# Unit-114.net
KiCad netlist of a schematic drawn in Altium Designer
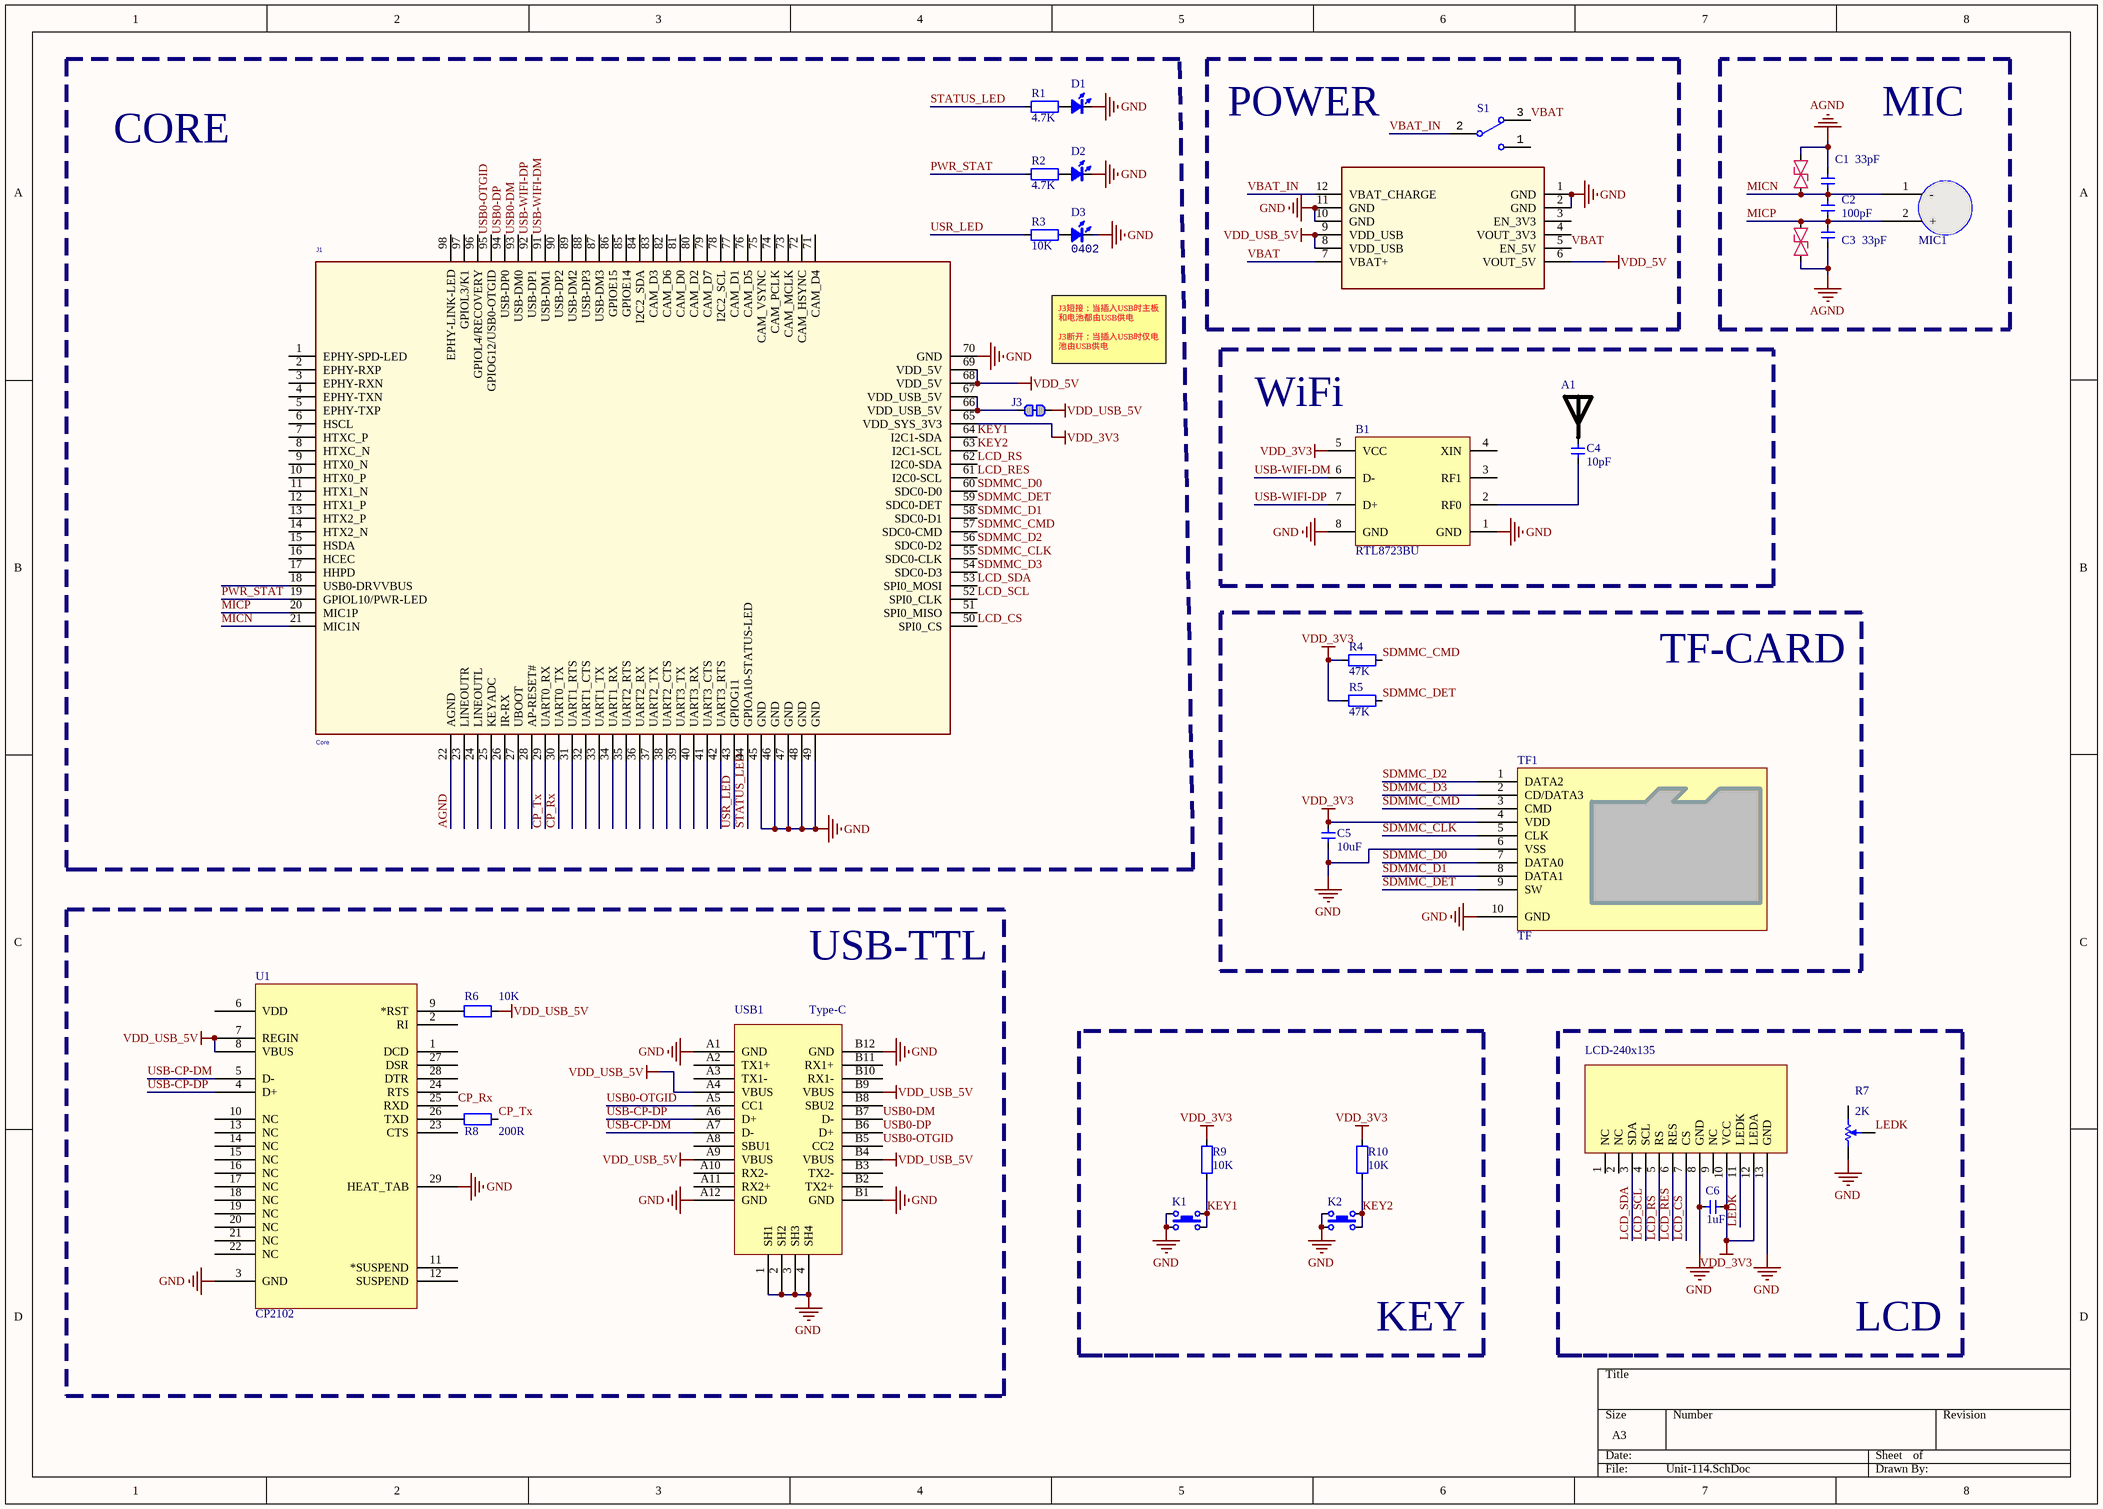
[diagram p0: Unit-114.SchDoc]

(export (version "E")
  (design (tool "Eeschema 10.0.6"))
  (components
    (comp (ref "1")
      (value "LCD-240x135")
      (footprint "LCD-240x135")
      (description "显示屏")
      (libsource (lib "MyPcbLib") (part "LCD-240x135"))
    )
    (comp (ref "A1")
      (value "RAINSUN")
      (footprint "ANT-Rainsun-AN5120")
      (libsource (lib "MyPcbLib") (part "ANT-Rainsun-AP5120"))
    )
    (comp (ref "B1")
      (value "RTL8723BU")
      (footprint "USB-WiFI-BT-RTL8723BU")
      (libsource (lib "MyPcbLib") (part "USB-WiFi-BT-RTL8723BU"))
    )
    (comp (ref "C1")
      (value "33pF")
      (footprint "CAP_0402")
      (description "Capacitor")
      (libsource (lib "MyPcbLib") (part "电容-0402"))
    )
    (comp (ref "C2")
      (value "100pF")
      (footprint "CAP_0402")
      (description "Capacitor")
      (libsource (lib "MyPcbLib") (part "电容-0402"))
    )
    (comp (ref "C3")
      (value "33pF")
      (footprint "CAP_0402")
      (description "Capacitor")
      (libsource (lib "MyPcbLib") (part "电容-0402"))
    )
    (comp (ref "C4")
      (value "10pF")
      (footprint "CAP_0402")
      (description "Capacitor")
      (libsource (lib "MyPcbLib") (part "电容-0402"))
    )
    (comp (ref "C5")
      (value "10uF")
      (footprint "CAP_0402")
      (description "Capacitor")
      (libsource (lib "MyPcbLib") (part "电容-0402"))
    )
    (comp (ref "C6")
      (value "1uF")
      (footprint "CAP_0402")
      (description "Capacitor")
      (libsource (lib "MyPcbLib") (part "电容-0402"))
    )
    (comp (ref "D1")
      (value "color?")
      (footprint "LED_0402_RED")
      (description "LED")
      (libsource (lib "KitSprout") (part "LED_0402"))
    )
    (comp (ref "D2")
      (value "color?")
      (footprint "LED_0402_YELLOW")
      (description "LED")
      (libsource (lib "KitSprout") (part "LED_0402"))
    )
    (comp (ref "D3")
      (value "color?")
      (footprint "LED_0402_BLUE")
      (description "LED")
      (fields (field (name "TYPE") "0402"))
      (libsource (lib "KitSprout") (part "LED_0402"))
    )
    (comp (ref "ESD-1")
      (value "ESD-0402")
      (footprint "ESD-0402")
      (description "ESD")
      (libsource (lib "MyPcbLib") (part "ESD-0402"))
    )
    (comp (ref "ESD-2")
      (value "ESD-0402")
      (footprint "ESD-0402")
      (description "ESD")
      (libsource (lib "MyPcbLib") (part "ESD-0402"))
    )
    (comp (ref "J1")
      (value "Core")
      (footprint "Quantum-Quark")
      (libsource (lib "mLib") (part "Quantum-Quark-Core"))
    )
    (comp (ref "J2")
      (value "Power")
      (footprint "Quantum-GLUON")
      (libsource (lib "MyPcbLib") (part "Quantum-Gluon-Power"))
    )
    (comp (ref "J3")
      (value "跳线")
      (footprint "0402-0R")
      (description "Resistor")
      (fields (field (name "PUBLISHER") "Altium Limited"))
      (libsource (lib "MyPcbLib") (part "跳线"))
    )
    (comp (ref "K1")
      (value "TACT 4P")
      (footprint "ButtonTACT_3.5*3.55_90")
      (description "Button")
      (libsource (lib "KitSprout") (part "ButtonTACT"))
    )
    (comp (ref "K2")
      (value "TACT 4P")
      (footprint "ButtonTACT_3.5*3.55_90")
      (description "Button")
      (libsource (lib "KitSprout") (part "ButtonTACT"))
    )
    (comp (ref "MIC1") (value "MIC*") (footprint "MIC-SMT") (libsource (lib "MyPcbLib") (part "MIC")))
    (comp (ref "R1")
      (value "4.7K")
      (footprint "RES_0402")
      (description "Resistor")
      (libsource (lib "MyPcbLib") (part "电阻-0402"))
    )
    (comp (ref "R2")
      (value "4.7K")
      (footprint "RES_0402")
      (description "Resistor")
      (libsource (lib "MyPcbLib") (part "电阻-0402"))
    )
    (comp (ref "R3")
      (value "10K")
      (footprint "RES_0402")
      (description "Resistor")
      (libsource (lib "MyPcbLib") (part "电阻-0402"))
    )
    (comp (ref "R4")
      (value "47K")
      (footprint "RES_0402")
      (description "Resistor")
      (libsource (lib "MyPcbLib") (part "电阻-0402"))
    )
    (comp (ref "R5")
      (value "47K")
      (footprint "RES_0402")
      (description "Resistor")
      (libsource (lib "MyPcbLib") (part "电阻-0402"))
    )
    (comp (ref "R6")
      (value "10K")
      (footprint "RES_0402")
      (description "Resistor")
      (libsource (lib "") (part "电阻-0402_2"))
    )
    (comp (ref "R7")
      (value "2K")
      (footprint "贴片电位器 3*3")
      (fields (field (name "PUBLISHER") "Altium Limited"))
      (libsource (lib "MyPcbLib") (part "电位器-贴片"))
    )
    (comp (ref "R8")
      (value "200R")
      (footprint "RES_0402")
      (description "Resistor")
      (libsource (lib "") (part "电阻-0402_2"))
    )
    (comp (ref "R9")
      (value "10K")
      (footprint "RES_0402")
      (description "Resistor")
      (libsource (lib "") (part "电阻-0402_1"))
    )
    (comp (ref "R10")
      (value "10K")
      (footprint "RES_0402")
      (description "Resistor")
      (libsource (lib "") (part "电阻-0402_1"))
    )
    (comp (ref "S1")
      (value "SPDT 3P")
      (footprint "SwitchSPDT_2.8X6.6_90")
      (description "Switch")
      (libsource (lib "KitSprout") (part "SwitchSPDT_2.8x6.6_90"))
    )
    (comp (ref "TF1")
      (value "TF")
      (footprint "TF-SOCKET - short")
      (description "8脚自弹")
      (libsource (lib "MyPcbLib") (part "TF卡座"))
    )
    (comp (ref "U1")
      (value "CP2102")
      (footprint "QFN-28")
      (description "USB转TTL")
      (libsource (lib "mLib") (part "CP2102"))
    )
    (comp (ref "USB1")
      (value "Type-C")
      (footprint "Type-C-TOP")
      (libsource (lib "MyPcbLib") (part "USB-Type-C-TOP"))
    )
  )
  (nets
    (net (code "1") (name "/CP_Rx") (class "Default")
      (node (ref "J1") (pin "30") (pinfunction "UART0_TX_30") (pintype "passive"))
      (node (ref "U1") (pin "25") (pinfunction "RXD_25") (pintype "passive"))
    )
    (net (code "2") (name "/CP_Tx") (class "Default")
      (node (ref "J1") (pin "29") (pinfunction "UART0_RX_29") (pintype "passive"))
      (node (ref "R8") (pin "1") (pinfunction "1_1") (pintype "passive"))
    )
    (net (code "3") (name "/KEY1") (class "Default")
      (node (ref "J1") (pin "64") (pinfunction "I2C1-SDA_64") (pintype "passive"))
      (node (ref "K1") (pin "2") (pinfunction "2_2") (pintype "passive"))
      (node (ref "K1") (pin "4") (pinfunction "4_4") (pintype "passive"))
      (node (ref "R9") (pin "1") (pinfunction "1_1") (pintype "passive"))
    )
    (net (code "4") (name "/KEY2") (class "Default")
      (node (ref "J1") (pin "63") (pinfunction "I2C1-SCL_63") (pintype "passive"))
      (node (ref "K2") (pin "2") (pinfunction "2_2") (pintype "passive"))
      (node (ref "K2") (pin "4") (pinfunction "4_4") (pintype "passive"))
      (node (ref "R10") (pin "1") (pinfunction "1_1") (pintype "passive"))
    )
    (net (code "5") (name "/LCD_CS") (class "Default")
      (node (ref "1") (pin "7") (pinfunction "CS_7") (pintype "passive"))
      (node (ref "J1") (pin "50") (pinfunction "SPI0_CS_50") (pintype "passive"))
    )
    (net (code "6") (name "/LCD_RES") (class "Default")
      (node (ref "1") (pin "6") (pinfunction "RES_6") (pintype "passive"))
      (node (ref "J1") (pin "61") (pinfunction "I2C0-SCL_61") (pintype "passive"))
    )
    (net (code "7") (name "/LCD_RS") (class "Default")
      (node (ref "1") (pin "5") (pinfunction "RS_5") (pintype "passive"))
      (node (ref "J1") (pin "62") (pinfunction "I2C0-SDA_62") (pintype "passive"))
    )
    (net (code "8") (name "/LCD_SCL") (class "Default")
      (node (ref "1") (pin "4") (pinfunction "SCL_4") (pintype "passive"))
      (node (ref "J1") (pin "52") (pinfunction "SPI0_CLK_52") (pintype "passive"))
    )
    (net (code "9") (name "/LCD_SDA") (class "Default")
      (node (ref "1") (pin "3") (pinfunction "SDA_3") (pintype "passive"))
      (node (ref "J1") (pin "53") (pinfunction "SPI0_MOSI_53") (pintype "passive"))
    )
    (net (code "10") (name "/LEDK") (class "Default")
      (node (ref "1") (pin "11") (pinfunction "LEDK_11") (pintype "passive"))
      (node (ref "R7") (pin "3") (pinfunction "W_3") (pintype "passive"))
    )
    (net (code "11") (name "/MICN") (class "Default")
      (node (ref "C1") (pin "2") (pinfunction "2_2") (pintype "passive"))
      (node (ref "C2") (pin "2") (pinfunction "2_2") (pintype "passive"))
      (node (ref "ESD-1") (pin "1") (pinfunction "1_1") (pintype "passive"))
      (node (ref "J1") (pin "21") (pinfunction "MIC1N_21") (pintype "passive"))
      (node (ref "MIC1") (pin "1") (pinfunction "-_1") (pintype "passive"))
    )
    (net (code "12") (name "/MICP") (class "Default")
      (node (ref "C2") (pin "1") (pinfunction "1_1") (pintype "passive"))
      (node (ref "C3") (pin "2") (pinfunction "2_2") (pintype "passive"))
      (node (ref "ESD-2") (pin "2") (pinfunction "2_2") (pintype "passive"))
      (node (ref "J1") (pin "20") (pinfunction "MIC1P_20") (pintype "passive"))
      (node (ref "MIC1") (pin "2") (pinfunction "+_2") (pintype "passive"))
    )
    (net (code "13") (name "/PWR_STAT") (class "Default")
      (node (ref "J1") (pin "19") (pinfunction "GPIOL10/PWR-LED_19") (pintype "passive"))
      (node (ref "R2") (pin "1") (pinfunction "1_1") (pintype "passive"))
    )
    (net (code "14") (name "/SDMMC_CLK") (class "Default")
      (node (ref "J1") (pin "55") (pinfunction "SDC0-CLK_55") (pintype "passive"))
      (node (ref "TF1") (pin "5") (pinfunction "CLK_5") (pintype "passive"))
    )
    (net (code "15") (name "/SDMMC_CMD") (class "Default")
      (node (ref "J1") (pin "57") (pinfunction "SDC0-CMD_57") (pintype "passive"))
      (node (ref "R4") (pin "2") (pinfunction "2_2") (pintype "passive"))
      (node (ref "TF1") (pin "3") (pinfunction "CMD_3") (pintype "passive"))
    )
    (net (code "16") (name "/SDMMC_D0") (class "Default")
      (node (ref "J1") (pin "60") (pinfunction "SDC0-D0_60") (pintype "passive"))
      (node (ref "TF1") (pin "7") (pinfunction "DATA0_7") (pintype "passive"))
    )
    (net (code "17") (name "/SDMMC_D1") (class "Default")
      (node (ref "J1") (pin "58") (pinfunction "SDC0-D1_58") (pintype "passive"))
      (node (ref "TF1") (pin "8") (pinfunction "DATA1_8") (pintype "passive"))
    )
    (net (code "18") (name "/SDMMC_D2") (class "Default")
      (node (ref "J1") (pin "56") (pinfunction "SDC0-D2_56") (pintype "passive"))
      (node (ref "TF1") (pin "1") (pinfunction "DATA2_1") (pintype "passive"))
    )
    (net (code "19") (name "/SDMMC_D3") (class "Default")
      (node (ref "J1") (pin "54") (pinfunction "SDC0-D3_54") (pintype "passive"))
      (node (ref "TF1") (pin "2") (pinfunction "CD/DATA3_2") (pintype "passive"))
    )
    (net (code "20") (name "/SDMMC_DET") (class "Default")
      (node (ref "J1") (pin "59") (pinfunction "SDC0-DET_59") (pintype "passive"))
      (node (ref "R5") (pin "2") (pinfunction "2_2") (pintype "passive"))
      (node (ref "TF1") (pin "9") (pinfunction "SW_9") (pintype "passive"))
    )
    (net (code "21") (name "/STATUS_LED") (class "Default")
      (node (ref "J1") (pin "44") (pinfunction "GPIOA10-STATUS-LED_44") (pintype "passive"))
      (node (ref "R1") (pin "1") (pinfunction "1_1") (pintype "passive"))
    )
    (net (code "22") (name "/USB-CP-DM") (class "Default")
      (node (ref "U1") (pin "5") (pinfunction "D-_5") (pintype "passive"))
      (node (ref "USB1") (pin "A7") (pinfunction "D-_A7") (pintype "passive"))
    )
    (net (code "23") (name "/USB-CP-DP") (class "Default")
      (node (ref "U1") (pin "4") (pinfunction "D+_4") (pintype "passive"))
      (node (ref "USB1") (pin "A6") (pinfunction "D+_A6") (pintype "passive"))
    )
    (net (code "24") (name "/USB-WIFI-DM") (class "Default")
      (node (ref "B1") (pin "6") (pinfunction "D-_6") (pintype "passive"))
      (node (ref "J1") (pin "91") (pinfunction "USB-DM1_91") (pintype "passive"))
    )
    (net (code "25") (name "/USB-WIFI-DP") (class "Default")
      (node (ref "B1") (pin "7") (pinfunction "D+_7") (pintype "passive"))
      (node (ref "J1") (pin "92") (pinfunction "USB-DP1_92") (pintype "passive"))
    )
    (net (code "26") (name "/USB0-DM") (class "Default")
      (node (ref "J1") (pin "93") (pinfunction "USB-DM0_93") (pintype "passive"))
      (node (ref "USB1") (pin "B7") (pinfunction "D-_B7") (pintype "passive"))
    )
    (net (code "27") (name "/USB0-DP") (class "Default")
      (node (ref "J1") (pin "94") (pinfunction "USB-DP0_94") (pintype "passive"))
      (node (ref "USB1") (pin "B6") (pinfunction "D+_B6") (pintype "passive"))
    )
    (net (code "28") (name "/USB0-OTGID") (class "Default")
      (node (ref "J1") (pin "95") (pinfunction "GPIOG12/USB0-OTGID_95") (pintype "passive"))
      (node (ref "USB1") (pin "A5") (pinfunction "CC1_A5") (pintype "passive"))
      (node (ref "USB1") (pin "B5") (pinfunction "CC2_B5") (pintype "passive"))
    )
    (net (code "29") (name "/USR_LED") (class "Default")
      (node (ref "J1") (pin "43") (pinfunction "GPIOG11_43") (pintype "passive"))
      (node (ref "R3") (pin "1") (pinfunction "1_1") (pintype "passive"))
    )
    (net (code "30") (name "/VBAT") (class "Default")
      (node (ref "J2") (pin "5") (pinfunction "EN_5V_5") (pintype "passive"))
      (node (ref "J2") (pin "7") (pinfunction "VBAT+_7") (pintype "passive"))
      (node (ref "S1") (pin "3") (pinfunction "3_3") (pintype "passive"))
    )
    (net (code "31") (name "/VBAT_IN") (class "Default")
      (node (ref "J2") (pin "12") (pinfunction "VBAT_CHARGE_12") (pintype "passive"))
      (node (ref "S1") (pin "2") (pinfunction "2_2") (pintype "passive"))
    )
    (net (code "32") (name "AGND") (class "Default")
      (node (ref "C1") (pin "1") (pinfunction "1_1") (pintype "passive"))
      (node (ref "C3") (pin "1") (pinfunction "1_1") (pintype "passive"))
      (node (ref "ESD-1") (pin "2") (pinfunction "2_2") (pintype "passive"))
      (node (ref "ESD-2") (pin "1") (pinfunction "1_1") (pintype "passive"))
      (node (ref "J1") (pin "22") (pinfunction "AGND_22") (pintype "passive"))
    )
    (net (code "33") (name "GND") (class "Default")
      (node (ref "1") (pin "13") (pinfunction "GND_13") (pintype "passive"))
      (node (ref "1") (pin "8") (pinfunction "GND_8") (pintype "passive"))
      (node (ref "B1") (pin "1") (pinfunction "GND_1") (pintype "passive"))
      (node (ref "B1") (pin "8") (pinfunction "GND_8") (pintype "passive"))
      (node (ref "C5") (pin "1") (pinfunction "1_1") (pintype "passive"))
      (node (ref "C6") (pin "2") (pinfunction "2_2") (pintype "passive"))
      (node (ref "D1") (pin "2") (pinfunction "K_2") (pintype "passive"))
      (node (ref "D2") (pin "2") (pinfunction "K_2") (pintype "passive"))
      (node (ref "D3") (pin "2") (pinfunction "K_2") (pintype "passive"))
      (node (ref "J1") (pin "45") (pinfunction "GND_45") (pintype "passive"))
      (node (ref "J1") (pin "46") (pinfunction "GND_46") (pintype "passive"))
      (node (ref "J1") (pin "47") (pinfunction "GND_47") (pintype "passive"))
      (node (ref "J1") (pin "48") (pinfunction "GND_48") (pintype "passive"))
      (node (ref "J1") (pin "49") (pinfunction "GND_49") (pintype "passive"))
      (node (ref "J1") (pin "70") (pinfunction "GND_70") (pintype "passive"))
      (node (ref "J2") (pin "1") (pinfunction "GND_1") (pintype "passive"))
      (node (ref "J2") (pin "10") (pinfunction "GND_10") (pintype "passive"))
      (node (ref "J2") (pin "11") (pinfunction "GND_11") (pintype "passive"))
      (node (ref "J2") (pin "2") (pinfunction "GND_2") (pintype "passive"))
      (node (ref "K1") (pin "1") (pinfunction "1_1") (pintype "passive"))
      (node (ref "K1") (pin "3") (pinfunction "3_3") (pintype "passive"))
      (node (ref "K2") (pin "1") (pinfunction "1_1") (pintype "passive"))
      (node (ref "K2") (pin "3") (pinfunction "3_3") (pintype "passive"))
      (node (ref "R7") (pin "2") (pinfunction "-_2") (pintype "passive"))
      (node (ref "TF1") (pin "10") (pinfunction "GND_10") (pintype "passive"))
      (node (ref "TF1") (pin "6") (pinfunction "VSS_6") (pintype "passive"))
      (node (ref "U1") (pin "29") (pinfunction "HEAT_TAB_29") (pintype "passive"))
      (node (ref "U1") (pin "3") (pinfunction "GND_3") (pintype "passive"))
      (node (ref "USB1") (pin "1") (pinfunction "SH1_1") (pintype "passive"))
      (node (ref "USB1") (pin "2") (pinfunction "SH2_2") (pintype "passive"))
      (node (ref "USB1") (pin "3") (pinfunction "SH3_3") (pintype "passive"))
      (node (ref "USB1") (pin "4") (pinfunction "SH4_4") (pintype "passive"))
      (node (ref "USB1") (pin "A1") (pinfunction "GND_A1") (pintype "passive"))
      (node (ref "USB1") (pin "A12") (pinfunction "GND_A12") (pintype "passive"))
      (node (ref "USB1") (pin "B1") (pinfunction "GND_B1") (pintype "passive"))
      (node (ref "USB1") (pin "B12") (pinfunction "GND_B12") (pintype "passive"))
    )
    (net (code "34") (name "Net-(A1-Pad1)") (class "Default")
      (node (ref "A1") (pin "1") (pinfunction "1_1") (pintype "passive"))
      (node (ref "C4") (pin "1") (pinfunction "1_1") (pintype "passive"))
    )
    (net (code "35") (name "Net-(B1-RF0)") (class "Default")
      (node (ref "B1") (pin "2") (pinfunction "RF0_2") (pintype "passive"))
      (node (ref "C4") (pin "2") (pinfunction "2_2") (pintype "passive"))
    )
    (net (code "36") (name "Net-(D1-A)") (class "Default")
      (node (ref "D1") (pin "1") (pinfunction "A_1") (pintype "passive"))
      (node (ref "R1") (pin "2") (pinfunction "2_2") (pintype "passive"))
    )
    (net (code "37") (name "Net-(D2-A)") (class "Default")
      (node (ref "D2") (pin "1") (pinfunction "A_1") (pintype "passive"))
      (node (ref "R2") (pin "2") (pinfunction "2_2") (pintype "passive"))
    )
    (net (code "38") (name "Net-(D3-A)") (class "Default")
      (node (ref "D3") (pin "1") (pinfunction "A_1") (pintype "passive"))
      (node (ref "R3") (pin "2") (pinfunction "2_2") (pintype "passive"))
    )
    (net (code "39") (name "Net-(J1-VDD_USB_5V-Pad66)") (class "Default")
      (node (ref "J1") (pin "66") (pinfunction "VDD_USB_5V_66") (pintype "passive"))
      (node (ref "J1") (pin "67") (pinfunction "VDD_USB_5V_67") (pintype "passive"))
      (node (ref "J3") (pin "1") (pinfunction "1_1") (pintype "passive"))
    )
    (net (code "40") (name "Net-(U1-*RST)") (class "Default")
      (node (ref "R6") (pin "2") (pinfunction "2_2") (pintype "passive"))
      (node (ref "U1") (pin "9") (pinfunction "*RST_9") (pintype "passive"))
    )
    (net (code "41") (name "Net-(U1-TXD)") (class "Default")
      (node (ref "R8") (pin "2") (pinfunction "2_2") (pintype "passive"))
      (node (ref "U1") (pin "26") (pinfunction "TXD_26") (pintype "passive"))
    )
    (net (code "42") (name "VDD_3V3") (class "Default")
      (node (ref "1") (pin "10") (pinfunction "VCC_10") (pintype "passive"))
      (node (ref "1") (pin "12") (pinfunction "LEDA_12") (pintype "passive"))
      (node (ref "B1") (pin "5") (pinfunction "VCC_5") (pintype "passive"))
      (node (ref "C5") (pin "2") (pinfunction "2_2") (pintype "passive"))
      (node (ref "C6") (pin "1") (pinfunction "1_1") (pintype "passive"))
      (node (ref "J1") (pin "65") (pinfunction "VDD_SYS_3V3_65") (pintype "passive"))
      (node (ref "R10") (pin "2") (pinfunction "2_2") (pintype "passive"))
      (node (ref "R4") (pin "1") (pinfunction "1_1") (pintype "passive"))
      (node (ref "R5") (pin "1") (pinfunction "1_1") (pintype "passive"))
      (node (ref "R9") (pin "2") (pinfunction "2_2") (pintype "passive"))
      (node (ref "TF1") (pin "4") (pinfunction "VDD_4") (pintype "passive"))
    )
    (net (code "43") (name "VDD_5V") (class "Default")
      (node (ref "J1") (pin "68") (pinfunction "VDD_5V_68") (pintype "passive"))
      (node (ref "J1") (pin "69") (pinfunction "VDD_5V_69") (pintype "passive"))
      (node (ref "J2") (pin "6") (pinfunction "VOUT_5V_6") (pintype "passive"))
    )
    (net (code "44") (name "VDD_USB_5V") (class "Default")
      (node (ref "J2") (pin "8") (pinfunction "VDD_USB_8") (pintype "passive"))
      (node (ref "J2") (pin "9") (pinfunction "VDD_USB_9") (pintype "passive"))
      (node (ref "J3") (pin "2") (pinfunction "2_2") (pintype "passive"))
      (node (ref "R6") (pin "1") (pinfunction "1_1") (pintype "passive"))
      (node (ref "U1") (pin "7") (pinfunction "REGIN_7") (pintype "passive"))
      (node (ref "U1") (pin "8") (pinfunction "VBUS_8") (pintype "passive"))
      (node (ref "USB1") (pin "A4") (pinfunction "VBUS_A4") (pintype "passive"))
      (node (ref "USB1") (pin "A9") (pinfunction "VBUS_A9") (pintype "passive"))
      (node (ref "USB1") (pin "B4") (pinfunction "VBUS_B4") (pintype "passive"))
      (node (ref "USB1") (pin "B9") (pinfunction "VBUS_B9") (pintype "passive"))
    )
    (net (code "45") (name "unconnected-(1-NC-Pad1)") (class "Default")
      (node (ref "1") (pin "1") (pinfunction "NC_1") (pintype "passive"))
    )
    (net (code "46") (name "unconnected-(1-NC-Pad2)") (class "Default")
      (node (ref "1") (pin "2") (pinfunction "NC_2") (pintype "passive"))
    )
    (net (code "47") (name "unconnected-(1-NC-Pad9)") (class "Default")
      (node (ref "1") (pin "9") (pinfunction "NC_9") (pintype "passive"))
    )
    (net (code "48") (name "unconnected-(B1-RF1-Pad3)") (class "Default")
      (node (ref "B1") (pin "3") (pinfunction "RF1_3") (pintype "passive"))
    )
    (net (code "49") (name "unconnected-(B1-XIN-Pad4)") (class "Default")
      (node (ref "B1") (pin "4") (pinfunction "XIN_4") (pintype "passive"))
    )
    (net (code "50") (name "unconnected-(J1-AP-RESET#-Pad28)") (class "Default")
      (node (ref "J1") (pin "28") (pinfunction "AP-RESET#_28") (pintype "passive"))
    )
    (net (code "51") (name "unconnected-(J1-CAM_D0-Pad81)") (class "Default")
      (node (ref "J1") (pin "81") (pinfunction "CAM_D0_81") (pintype "passive"))
    )
    (net (code "52") (name "unconnected-(J1-CAM_D1-Pad77)") (class "Default")
      (node (ref "J1") (pin "77") (pinfunction "CAM_D1_77") (pintype "passive"))
    )
    (net (code "53") (name "unconnected-(J1-CAM_D2-Pad80)") (class "Default")
      (node (ref "J1") (pin "80") (pinfunction "CAM_D2_80") (pintype "passive"))
    )
    (net (code "54") (name "unconnected-(J1-CAM_D3-Pad83)") (class "Default")
      (node (ref "J1") (pin "83") (pinfunction "CAM_D3_83") (pintype "passive"))
    )
    (net (code "55") (name "unconnected-(J1-CAM_D4-Pad71)") (class "Default")
      (node (ref "J1") (pin "71") (pinfunction "CAM_D4_71") (pintype "passive"))
    )
    (net (code "56") (name "unconnected-(J1-CAM_D5-Pad76)") (class "Default")
      (node (ref "J1") (pin "76") (pinfunction "CAM_D5_76") (pintype "passive"))
    )
    (net (code "57") (name "unconnected-(J1-CAM_D6-Pad82)") (class "Default")
      (node (ref "J1") (pin "82") (pinfunction "CAM_D6_82") (pintype "passive"))
    )
    (net (code "58") (name "unconnected-(J1-CAM_D7-Pad79)") (class "Default")
      (node (ref "J1") (pin "79") (pinfunction "CAM_D7_79") (pintype "passive"))
    )
    (net (code "59") (name "unconnected-(J1-CAM_HSYNC-Pad72)") (class "Default")
      (node (ref "J1") (pin "72") (pinfunction "CAM_HSYNC_72") (pintype "passive"))
    )
    (net (code "60") (name "unconnected-(J1-CAM_MCLK-Pad73)") (class "Default")
      (node (ref "J1") (pin "73") (pinfunction "CAM_MCLK_73") (pintype "passive"))
    )
    (net (code "61") (name "unconnected-(J1-CAM_PCLK-Pad74)") (class "Default")
      (node (ref "J1") (pin "74") (pinfunction "CAM_PCLK_74") (pintype "passive"))
    )
    (net (code "62") (name "unconnected-(J1-CAM_VSYNC-Pad75)") (class "Default")
      (node (ref "J1") (pin "75") (pinfunction "CAM_VSYNC_75") (pintype "passive"))
    )
    (net (code "63") (name "unconnected-(J1-EPHY-LINK-LED-Pad98)") (class "Default")
      (node (ref "J1") (pin "98") (pinfunction "EPHY-LINK-LED_98") (pintype "passive"))
    )
    (net (code "64") (name "unconnected-(J1-EPHY-RXN-Pad3)") (class "Default")
      (node (ref "J1") (pin "3") (pinfunction "EPHY-RXN_3") (pintype "passive"))
    )
    (net (code "65") (name "unconnected-(J1-EPHY-RXP-Pad2)") (class "Default")
      (node (ref "J1") (pin "2") (pinfunction "EPHY-RXP_2") (pintype "passive"))
    )
    (net (code "66") (name "unconnected-(J1-EPHY-SPD-LED-Pad1)") (class "Default")
      (node (ref "J1") (pin "1") (pinfunction "EPHY-SPD-LED_1") (pintype "passive"))
    )
    (net (code "67") (name "unconnected-(J1-EPHY-TXN-Pad4)") (class "Default")
      (node (ref "J1") (pin "4") (pinfunction "EPHY-TXN_4") (pintype "passive"))
    )
    (net (code "68") (name "unconnected-(J1-EPHY-TXP-Pad5)") (class "Default")
      (node (ref "J1") (pin "5") (pinfunction "EPHY-TXP_5") (pintype "passive"))
    )
    (net (code "69") (name "unconnected-(J1-GPIOE14-Pad85)") (class "Default")
      (node (ref "J1") (pin "85") (pinfunction "GPIOE14_85") (pintype "passive"))
    )
    (net (code "70") (name "unconnected-(J1-GPIOE15-Pad86)") (class "Default")
      (node (ref "J1") (pin "86") (pinfunction "GPIOE15_86") (pintype "passive"))
    )
    (net (code "71") (name "unconnected-(J1-GPIOL3{slash}K1-Pad97)") (class "Default")
      (node (ref "J1") (pin "97") (pinfunction "GPIOL3/K1_97") (pintype "passive"))
    )
    (net (code "72") (name "unconnected-(J1-GPIOL4{slash}RECOVERY-Pad96)") (class "Default")
      (node (ref "J1") (pin "96") (pinfunction "GPIOL4/RECOVERY_96") (pintype "passive"))
    )
    (net (code "73") (name "unconnected-(J1-HCEC-Pad16)") (class "Default")
      (node (ref "J1") (pin "16") (pinfunction "HCEC_16") (pintype "passive"))
    )
    (net (code "74") (name "unconnected-(J1-HHPD-Pad17)") (class "Default")
      (node (ref "J1") (pin "17") (pinfunction "HHPD_17") (pintype "passive"))
    )
    (net (code "75") (name "unconnected-(J1-HSCL-Pad6)") (class "Default")
      (node (ref "J1") (pin "6") (pinfunction "HSCL_6") (pintype "passive"))
    )
    (net (code "76") (name "unconnected-(J1-HSDA-Pad15)") (class "Default")
      (node (ref "J1") (pin "15") (pinfunction "HSDA_15") (pintype "passive"))
    )
    (net (code "77") (name "unconnected-(J1-HTX0_N-Pad9)") (class "Default")
      (node (ref "J1") (pin "9") (pinfunction "HTX0_N_9") (pintype "passive"))
    )
    (net (code "78") (name "unconnected-(J1-HTX0_P-Pad10)") (class "Default")
      (node (ref "J1") (pin "10") (pinfunction "HTX0_P_10") (pintype "passive"))
    )
    (net (code "79") (name "unconnected-(J1-HTX1_N-Pad11)") (class "Default")
      (node (ref "J1") (pin "11") (pinfunction "HTX1_N_11") (pintype "passive"))
    )
    (net (code "80") (name "unconnected-(J1-HTX1_P-Pad12)") (class "Default")
      (node (ref "J1") (pin "12") (pinfunction "HTX1_P_12") (pintype "passive"))
    )
    (net (code "81") (name "unconnected-(J1-HTX2_N-Pad14)") (class "Default")
      (node (ref "J1") (pin "14") (pinfunction "HTX2_N_14") (pintype "passive"))
    )
    (net (code "82") (name "unconnected-(J1-HTX2_P-Pad13)") (class "Default")
      (node (ref "J1") (pin "13") (pinfunction "HTX2_P_13") (pintype "passive"))
    )
    (net (code "83") (name "unconnected-(J1-HTXC_N-Pad8)") (class "Default")
      (node (ref "J1") (pin "8") (pinfunction "HTXC_N_8") (pintype "passive"))
    )
    (net (code "84") (name "unconnected-(J1-HTXC_P-Pad7)") (class "Default")
      (node (ref "J1") (pin "7") (pinfunction "HTXC_P_7") (pintype "passive"))
    )
    (net (code "85") (name "unconnected-(J1-I2C2_SCL-Pad78)") (class "Default")
      (node (ref "J1") (pin "78") (pinfunction "I2C2_SCL_78") (pintype "passive"))
    )
    (net (code "86") (name "unconnected-(J1-I2C2_SDA-Pad84)") (class "Default")
      (node (ref "J1") (pin "84") (pinfunction "I2C2_SDA_84") (pintype "passive"))
    )
    (net (code "87") (name "unconnected-(J1-IR-RX-Pad26)") (class "Default")
      (node (ref "J1") (pin "26") (pinfunction "IR-RX_26") (pintype "passive"))
    )
    (net (code "88") (name "unconnected-(J1-KEYADC-Pad25)") (class "Default")
      (node (ref "J1") (pin "25") (pinfunction "KEYADC_25") (pintype "passive"))
    )
    (net (code "89") (name "unconnected-(J1-LINEOUTL-Pad24)") (class "Default")
      (node (ref "J1") (pin "24") (pinfunction "LINEOUTL_24") (pintype "passive"))
    )
    (net (code "90") (name "unconnected-(J1-LINEOUTR-Pad23)") (class "Default")
      (node (ref "J1") (pin "23") (pinfunction "LINEOUTR_23") (pintype "passive"))
    )
    (net (code "91") (name "unconnected-(J1-SPI0_MISO-Pad51)") (class "Default")
      (node (ref "J1") (pin "51") (pinfunction "SPI0_MISO_51") (pintype "passive"))
    )
    (net (code "92") (name "unconnected-(J1-UART1_CTS-Pad32)") (class "Default")
      (node (ref "J1") (pin "32") (pinfunction "UART1_CTS_32") (pintype "passive"))
    )
    (net (code "93") (name "unconnected-(J1-UART1_RTS-Pad31)") (class "Default")
      (node (ref "J1") (pin "31") (pinfunction "UART1_RTS_31") (pintype "passive"))
    )
    (net (code "94") (name "unconnected-(J1-UART1_RX-Pad34)") (class "Default")
      (node (ref "J1") (pin "34") (pinfunction "UART1_RX_34") (pintype "passive"))
    )
    (net (code "95") (name "unconnected-(J1-UART1_TX-Pad33)") (class "Default")
      (node (ref "J1") (pin "33") (pinfunction "UART1_TX_33") (pintype "passive"))
    )
    (net (code "96") (name "unconnected-(J1-UART2_CTS-Pad38)") (class "Default")
      (node (ref "J1") (pin "38") (pinfunction "UART2_CTS_38") (pintype "passive"))
    )
    (net (code "97") (name "unconnected-(J1-UART2_RTS-Pad35)") (class "Default")
      (node (ref "J1") (pin "35") (pinfunction "UART2_RTS_35") (pintype "passive"))
    )
    (net (code "98") (name "unconnected-(J1-UART2_RX-Pad36)") (class "Default")
      (node (ref "J1") (pin "36") (pinfunction "UART2_RX_36") (pintype "passive"))
    )
    (net (code "99") (name "unconnected-(J1-UART2_TX-Pad37)") (class "Default")
      (node (ref "J1") (pin "37") (pinfunction "UART2_TX_37") (pintype "passive"))
    )
    (net (code "100") (name "unconnected-(J1-UART3_CTS-Pad41)") (class "Default")
      (node (ref "J1") (pin "41") (pinfunction "UART3_CTS_41") (pintype "passive"))
    )
    (net (code "101") (name "unconnected-(J1-UART3_RTS-Pad42)") (class "Default")
      (node (ref "J1") (pin "42") (pinfunction "UART3_RTS_42") (pintype "passive"))
    )
    (net (code "102") (name "unconnected-(J1-UART3_RX-Pad40)") (class "Default")
      (node (ref "J1") (pin "40") (pinfunction "UART3_RX_40") (pintype "passive"))
    )
    (net (code "103") (name "unconnected-(J1-UART3_TX-Pad39)") (class "Default")
      (node (ref "J1") (pin "39") (pinfunction "UART3_TX_39") (pintype "passive"))
    )
    (net (code "104") (name "unconnected-(J1-UBOOT-Pad27)") (class "Default")
      (node (ref "J1") (pin "27") (pinfunction "UBOOT_27") (pintype "passive"))
    )
    (net (code "105") (name "unconnected-(J1-USB-DM2-Pad89)") (class "Default")
      (node (ref "J1") (pin "89") (pinfunction "USB-DM2_89") (pintype "passive"))
    )
    (net (code "106") (name "unconnected-(J1-USB-DM3-Pad87)") (class "Default")
      (node (ref "J1") (pin "87") (pinfunction "USB-DM3_87") (pintype "passive"))
    )
    (net (code "107") (name "unconnected-(J1-USB-DP2-Pad90)") (class "Default")
      (node (ref "J1") (pin "90") (pinfunction "USB-DP2_90") (pintype "passive"))
    )
    (net (code "108") (name "unconnected-(J1-USB-DP3-Pad88)") (class "Default")
      (node (ref "J1") (pin "88") (pinfunction "USB-DP3_88") (pintype "passive"))
    )
    (net (code "109") (name "unconnected-(J1-USB0-DRVVBUS-Pad18)") (class "Default")
      (node (ref "J1") (pin "18") (pinfunction "USB0-DRVVBUS_18") (pintype "passive"))
    )
    (net (code "110") (name "unconnected-(J2-EN_3V3-Pad3)") (class "Default")
      (node (ref "J2") (pin "3") (pinfunction "EN_3V3_3") (pintype "passive"))
    )
    (net (code "111") (name "unconnected-(J2-VOUT_3V3-Pad4)") (class "Default")
      (node (ref "J2") (pin "4") (pinfunction "VOUT_3V3_4") (pintype "passive"))
    )
    (net (code "112") (name "unconnected-(R7-+-Pad1)") (class "Default")
      (node (ref "R7") (pin "1") (pinfunction "+_1") (pintype "passive"))
    )
    (net (code "113") (name "unconnected-(S1-Pad1)") (class "Default")
      (node (ref "S1") (pin "1") (pinfunction "1_1") (pintype "passive"))
    )
    (net (code "114") (name "unconnected-(U1-*SUSPEND-Pad11)") (class "Default")
      (node (ref "U1") (pin "11") (pinfunction "*SUSPEND_11") (pintype "passive"))
    )
    (net (code "115") (name "unconnected-(U1-CTS-Pad23)") (class "Default")
      (node (ref "U1") (pin "23") (pinfunction "CTS_23") (pintype "passive"))
    )
    (net (code "116") (name "unconnected-(U1-DCD-Pad1)") (class "Default")
      (node (ref "U1") (pin "1") (pinfunction "DCD_1") (pintype "passive"))
    )
    (net (code "117") (name "unconnected-(U1-DSR-Pad27)") (class "Default")
      (node (ref "U1") (pin "27") (pinfunction "DSR_27") (pintype "passive"))
    )
    (net (code "118") (name "unconnected-(U1-DTR-Pad28)") (class "Default")
      (node (ref "U1") (pin "28") (pinfunction "DTR_28") (pintype "passive"))
    )
    (net (code "119") (name "unconnected-(U1-NC-Pad10)") (class "Default")
      (node (ref "U1") (pin "10") (pinfunction "NC_10") (pintype "passive"))
    )
    (net (code "120") (name "unconnected-(U1-NC-Pad13)") (class "Default")
      (node (ref "U1") (pin "13") (pinfunction "NC_13") (pintype "passive"))
    )
    (net (code "121") (name "unconnected-(U1-NC-Pad14)") (class "Default")
      (node (ref "U1") (pin "14") (pinfunction "NC_14") (pintype "passive"))
    )
    (net (code "122") (name "unconnected-(U1-NC-Pad15)") (class "Default")
      (node (ref "U1") (pin "15") (pinfunction "NC_15") (pintype "passive"))
    )
    (net (code "123") (name "unconnected-(U1-NC-Pad16)") (class "Default")
      (node (ref "U1") (pin "16") (pinfunction "NC_16") (pintype "passive"))
    )
    (net (code "124") (name "unconnected-(U1-NC-Pad17)") (class "Default")
      (node (ref "U1") (pin "17") (pinfunction "NC_17") (pintype "passive"))
    )
    (net (code "125") (name "unconnected-(U1-NC-Pad18)") (class "Default")
      (node (ref "U1") (pin "18") (pinfunction "NC_18") (pintype "passive"))
    )
    (net (code "126") (name "unconnected-(U1-NC-Pad19)") (class "Default")
      (node (ref "U1") (pin "19") (pinfunction "NC_19") (pintype "passive"))
    )
    (net (code "127") (name "unconnected-(U1-NC-Pad20)") (class "Default")
      (node (ref "U1") (pin "20") (pinfunction "NC_20") (pintype "passive"))
    )
    (net (code "128") (name "unconnected-(U1-NC-Pad21)") (class "Default")
      (node (ref "U1") (pin "21") (pinfunction "NC_21") (pintype "passive"))
    )
    (net (code "129") (name "unconnected-(U1-NC-Pad22)") (class "Default")
      (node (ref "U1") (pin "22") (pinfunction "NC_22") (pintype "passive"))
    )
    (net (code "130") (name "unconnected-(U1-RI-Pad2)") (class "Default")
      (node (ref "U1") (pin "2") (pinfunction "RI_2") (pintype "passive"))
    )
    (net (code "131") (name "unconnected-(U1-RTS-Pad24)") (class "Default")
      (node (ref "U1") (pin "24") (pinfunction "RTS_24") (pintype "passive"))
    )
    (net (code "132") (name "unconnected-(U1-SUSPEND-Pad12)") (class "Default")
      (node (ref "U1") (pin "12") (pinfunction "SUSPEND_12") (pintype "passive"))
    )
    (net (code "133") (name "unconnected-(U1-VDD-Pad6)") (class "Default")
      (node (ref "U1") (pin "6") (pinfunction "VDD_6") (pintype "passive"))
    )
    (net (code "134") (name "unconnected-(USB1-RX1+-PadB11)") (class "Default")
      (node (ref "USB1") (pin "B11") (pinfunction "RX1+_B11") (pintype "passive"))
    )
    (net (code "135") (name "unconnected-(USB1-RX1--PadB10)") (class "Default")
      (node (ref "USB1") (pin "B10") (pinfunction "RX1-_B10") (pintype "passive"))
    )
    (net (code "136") (name "unconnected-(USB1-RX2+-PadA11)") (class "Default")
      (node (ref "USB1") (pin "A11") (pinfunction "RX2+_A11") (pintype "passive"))
    )
    (net (code "137") (name "unconnected-(USB1-RX2--PadA10)") (class "Default")
      (node (ref "USB1") (pin "A10") (pinfunction "RX2-_A10") (pintype "passive"))
    )
    (net (code "138") (name "unconnected-(USB1-SBU1-PadA8)") (class "Default")
      (node (ref "USB1") (pin "A8") (pinfunction "SBU1_A8") (pintype "passive"))
    )
    (net (code "139") (name "unconnected-(USB1-SBU2-PadB8)") (class "Default")
      (node (ref "USB1") (pin "B8") (pinfunction "SBU2_B8") (pintype "passive"))
    )
    (net (code "140") (name "unconnected-(USB1-TX1+-PadA2)") (class "Default")
      (node (ref "USB1") (pin "A2") (pinfunction "TX1+_A2") (pintype "passive"))
    )
    (net (code "141") (name "unconnected-(USB1-TX1--PadA3)") (class "Default")
      (node (ref "USB1") (pin "A3") (pinfunction "TX1-_A3") (pintype "passive"))
    )
    (net (code "142") (name "unconnected-(USB1-TX2+-PadB2)") (class "Default")
      (node (ref "USB1") (pin "B2") (pinfunction "TX2+_B2") (pintype "passive"))
    )
    (net (code "143") (name "unconnected-(USB1-TX2--PadB3)") (class "Default")
      (node (ref "USB1") (pin "B3") (pinfunction "TX2-_B3") (pintype "passive"))
    )
  )
)
